# SCH_Yunis_PCB_2026-04-03.net
KiCad netlist of a schematic drawn in EasyEDA
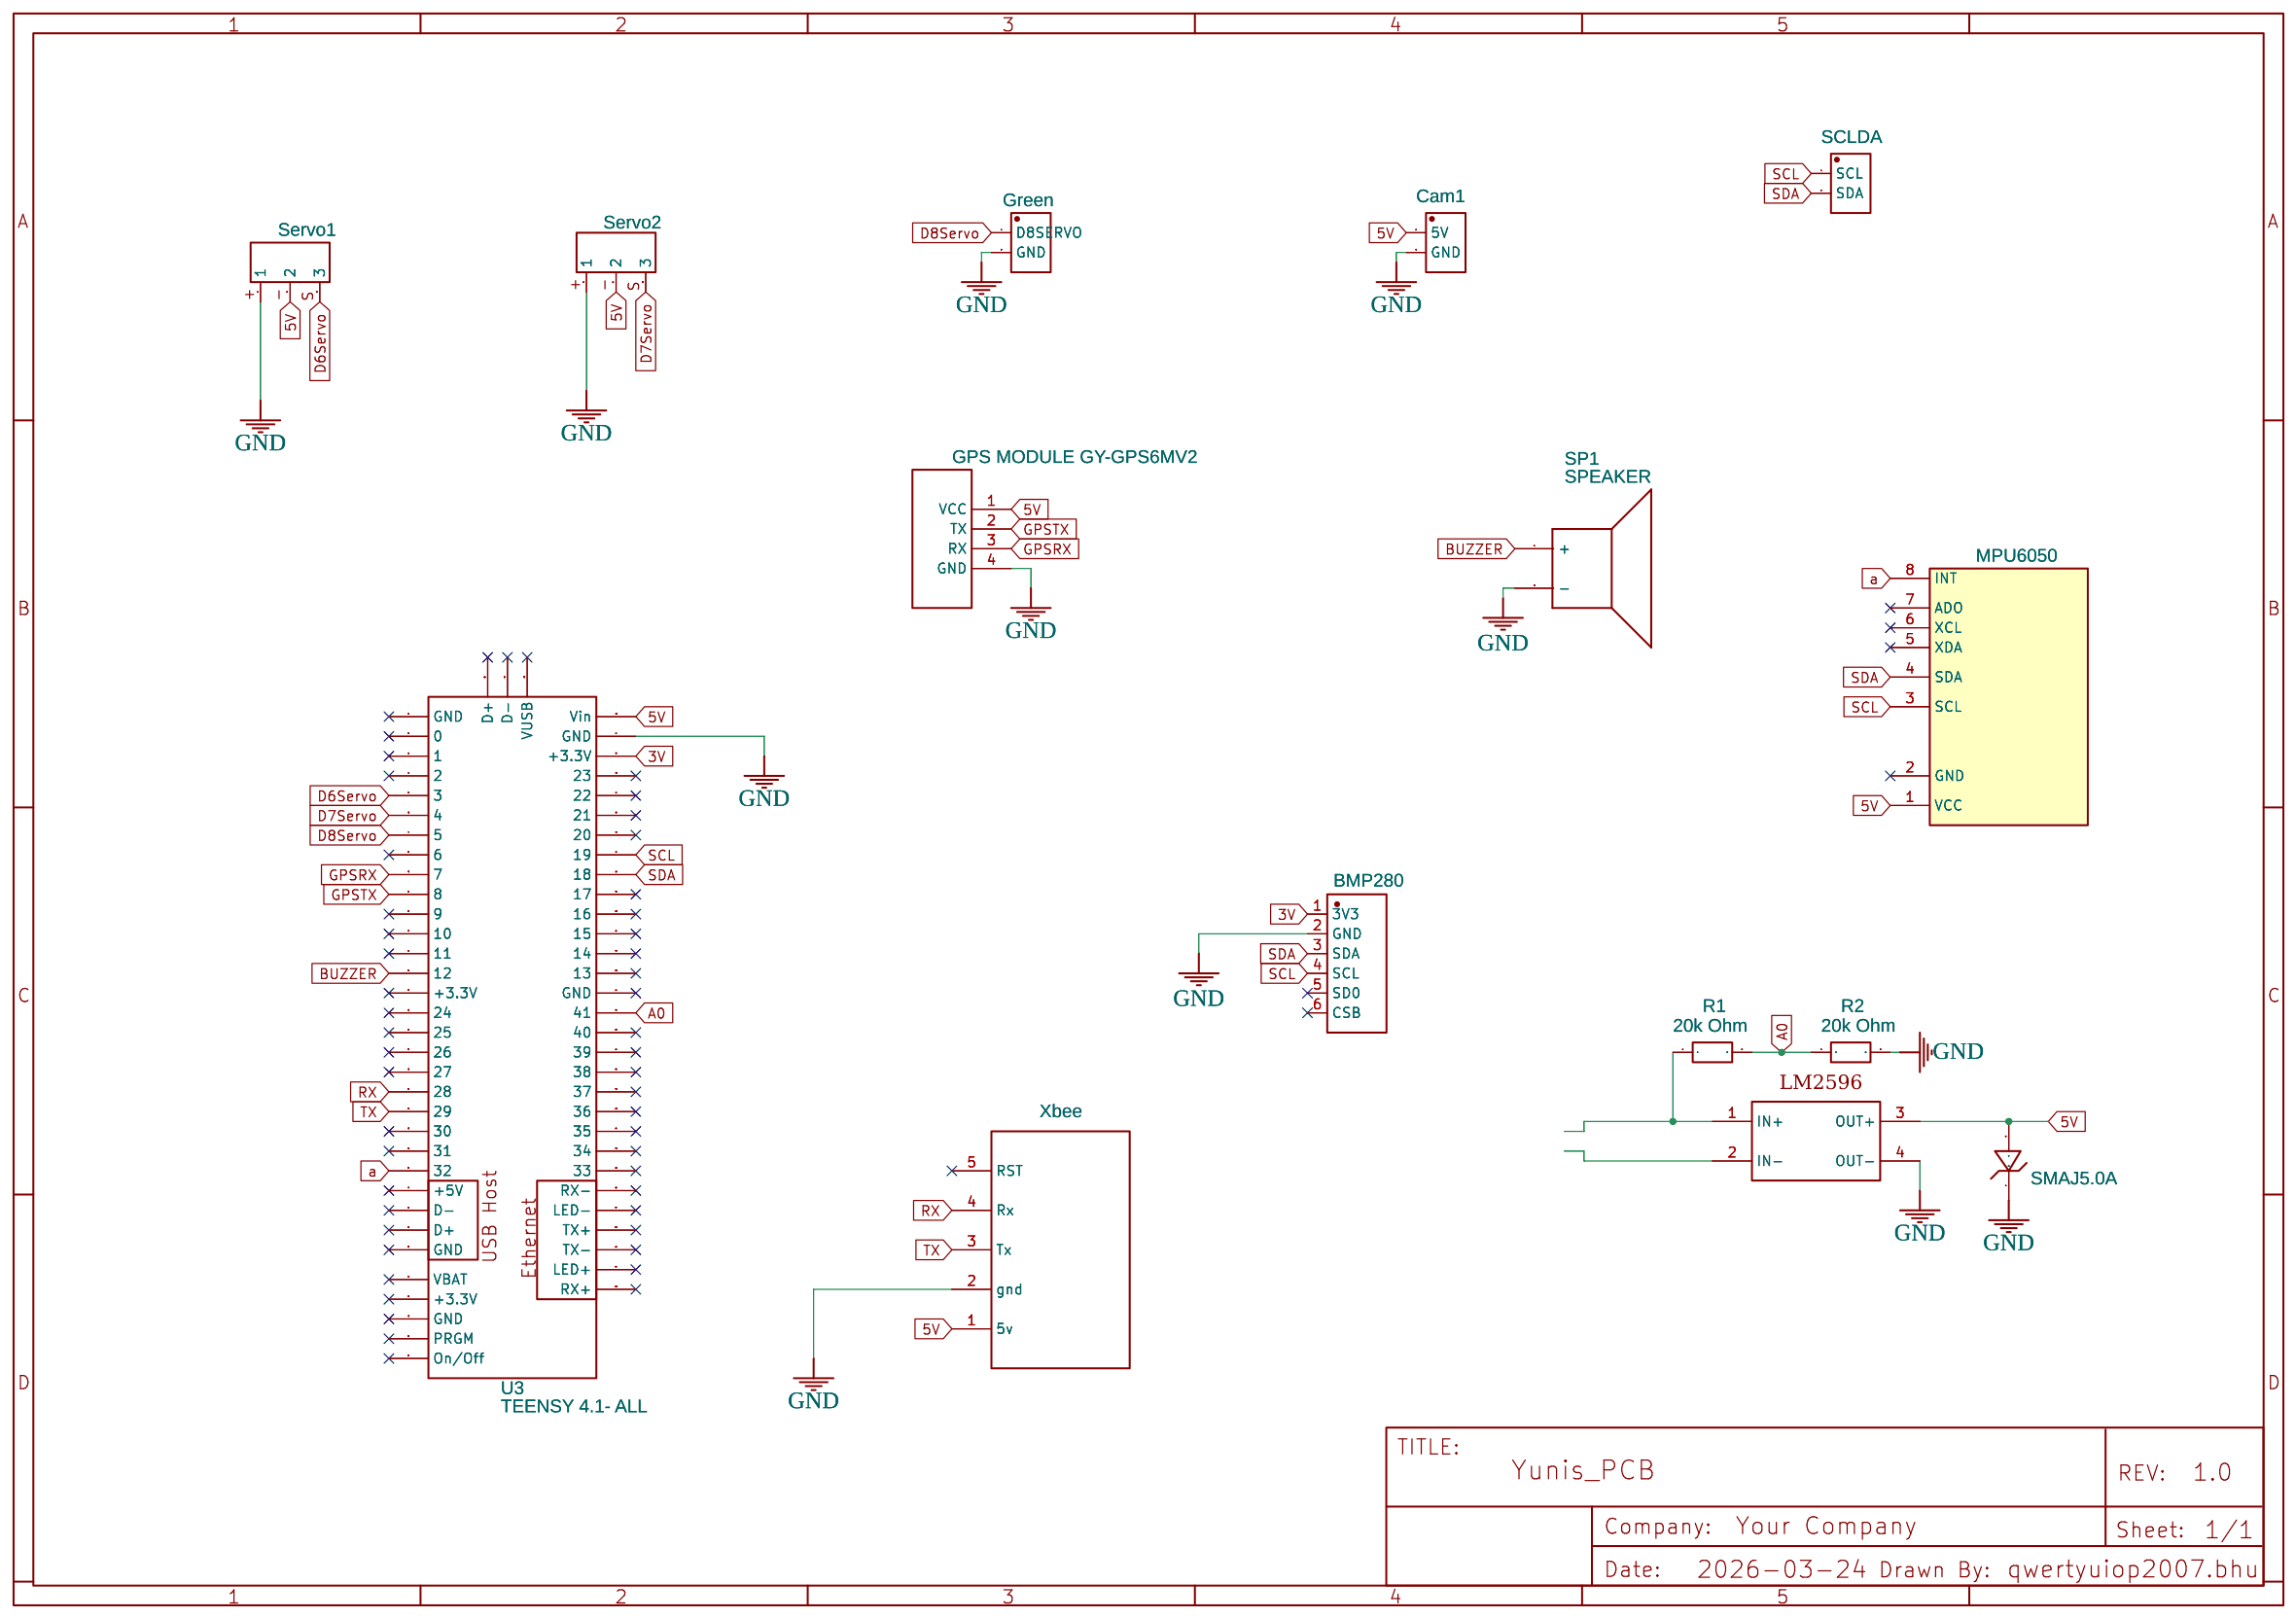
[diagram p0: schematic sheet]

(export (version "E")
  (design (tool "Eeschema 10.0.6"))
  (components
    (comp (ref "BUZZER1") (value "SCLDA") (libsource (lib "") (part "PINHEADER1x2_2")))
    (comp (ref "BUZZER2") (value "Cam1") (libsource (lib "") (part "PINHEADER1x2")))
    (comp (ref "BUZZER3") (value "Green") (libsource (lib "") (part "PINHEADER1x2_1")))
    (comp (ref "P1")
      (value "Servo2")
      (fields
        (field (name "Manufacturer Part") "Female headerHDR1X8-2.54")
        (field (name "Manufacturer") "BOOMELE")
      )
      (libsource (lib "") (part "HEADER PAD 3 PIN"))
    )
    (comp (ref "P2")
      (value "Servo1")
      (fields
        (field (name "Manufacturer Part") "Female headerHDR1X8-2.54")
        (field (name "Manufacturer") "BOOMELE")
      )
      (libsource (lib "") (part "HEADER PAD 3 PIN"))
    )
    (comp (ref "P3") (value "MPU6050") (libsource (lib "") (part "MPU6050")))
    (comp (ref "R1") (value "20k Ohm") (libsource (lib "") (part "R_0603_EU")))
    (comp (ref "R2") (value "20k Ohm") (libsource (lib "") (part "R_0603_EU")))
    (comp (ref "SP1") (value "SPEAKER") (libsource (lib "") (part "SPEAKER")))
    (comp (ref "U1") (value "GPS MODULE GY-GPS6MV2") (libsource (lib "") (part "GPS MODULE GY-GPS6MV2")))
    (comp (ref "U2") (value "BMP280") (libsource (lib "") (part "BMP280_C9900132626")))
    (comp (ref "U3") (value "TEENSY 4.1- ALL") (libsource (lib "") (part "TEENSY 4.1- ALL")))
    (comp (ref "U4")
      (value "BuckConverters_LM2596_Adj")
      (libsource (lib "") (part "BuckConverters_LM2596_Adj"))
    )
    (comp (ref "U5") (value "Xbee") (libsource (lib "") (part "Xbee Modulo")))
    (comp (ref "U6")
      (value "SMAJ5.0A")
      (fields (field (name "Manufacturer Part") "Littlefuse"))
      (libsource (lib "") (part "SMAJ5.0A"))
    )
  )
  (nets
    (net (code "1") (name "3V") (class "Default")
      (node (ref "U2") (pin "1") (pinfunction "3V3_1") (pintype "unspecified"))
      (node (ref "U3") (pin "46") (pinfunction "+3.3V_46") (pintype "unspecified"))
    )
    (net (code "2") (name "5V") (class "Default")
      (node (ref "BUZZER2") (pin "1") (pinfunction "5V_1") (pintype "unspecified"))
      (node (ref "P1") (pin "2") (pinfunction "2_2") (pintype "unspecified"))
      (node (ref "P2") (pin "2") (pinfunction "2_2") (pintype "unspecified"))
      (node (ref "P3") (pin "1") (pinfunction "VCC_1") (pintype "unspecified"))
      (node (ref "U1") (pin "1") (pinfunction "VCC_1") (pintype "unspecified"))
      (node (ref "U3") (pin "48") (pinfunction "Vin_48") (pintype "unspecified"))
      (node (ref "U4") (pin "3") (pinfunction "OUT+_3") (pintype "unspecified"))
      (node (ref "U5") (pin "1") (pinfunction "5v_1") (pintype "unspecified"))
      (node (ref "U6") (pin "2") (pinfunction "A_2") (pintype "unspecified"))
    )
    (net (code "3") (name "A0") (class "Default")
      (node (ref "R1") (pin "2") (pinfunction "2_2") (pintype "unspecified"))
      (node (ref "R2") (pin "1") (pinfunction "1_1") (pintype "unspecified"))
      (node (ref "U3") (pin "33") (pinfunction "41_33") (pintype "unspecified"))
    )
    (net (code "4") (name "BUZZER") (class "Default")
      (node (ref "SP1") (pin "1") (pinfunction "+_1") (pintype "bidirectional"))
      (node (ref "U3") (pin "14") (pinfunction "12_14") (pintype "unspecified"))
    )
    (net (code "5") (name "D6Servo") (class "Default")
      (node (ref "P2") (pin "3") (pinfunction "3_3") (pintype "unspecified"))
      (node (ref "U3") (pin "5") (pinfunction "3_5") (pintype "unspecified"))
    )
    (net (code "6") (name "D7Servo") (class "Default")
      (node (ref "P1") (pin "3") (pinfunction "3_3") (pintype "unspecified"))
      (node (ref "U3") (pin "6") (pinfunction "4_6") (pintype "unspecified"))
    )
    (net (code "7") (name "D8Servo") (class "Default")
      (node (ref "BUZZER3") (pin "1") (pinfunction "D8SERVO_1") (pintype "unspecified"))
      (node (ref "U3") (pin "7") (pinfunction "5_7") (pintype "unspecified"))
    )
    (net (code "8") (name "GND") (class "Default")
      (node (ref "BUZZER2") (pin "2") (pinfunction "GND_2") (pintype "unspecified"))
      (node (ref "BUZZER3") (pin "2") (pinfunction "GND_2") (pintype "unspecified"))
      (node (ref "P1") (pin "1") (pinfunction "1_1") (pintype "unspecified"))
      (node (ref "P2") (pin "1") (pinfunction "1_1") (pintype "unspecified"))
      (node (ref "R2") (pin "2") (pinfunction "2_2") (pintype "unspecified"))
      (node (ref "SP1") (pin "2") (pinfunction "-_2") (pintype "bidirectional"))
      (node (ref "U1") (pin "4") (pinfunction "GND_4") (pintype "unspecified"))
      (node (ref "U2") (pin "2") (pinfunction "GND_2") (pintype "unspecified"))
      (node (ref "U3") (pin "47") (pinfunction "GND_47") (pintype "unspecified"))
      (node (ref "U4") (pin "4") (pinfunction "OUT-_4") (pintype "unspecified"))
      (node (ref "U5") (pin "2") (pinfunction "gnd_2") (pintype "unspecified"))
      (node (ref "U6") (pin "1") (pinfunction "C_1") (pintype "unspecified"))
    )
    (net (code "9") (name "GPSRX") (class "Default")
      (node (ref "U1") (pin "3") (pinfunction "RX_3") (pintype "unspecified"))
      (node (ref "U3") (pin "9") (pinfunction "7_9") (pintype "unspecified"))
    )
    (net (code "10") (name "GPSTX") (class "Default")
      (node (ref "U1") (pin "2") (pinfunction "TX_2") (pintype "unspecified"))
      (node (ref "U3") (pin "10") (pinfunction "8_10") (pintype "unspecified"))
    )
    (net (code "11") (name "Net-(U4-IN+)") (class "Default")
      (node (ref "R1") (pin "1") (pinfunction "1_1") (pintype "unspecified"))
      (node (ref "U4") (pin "1") (pinfunction "IN+_1") (pintype "unspecified"))
    )
    (net (code "12") (name "RX") (class "Default")
      (node (ref "U3") (pin "20") (pinfunction "28_20") (pintype "unspecified"))
      (node (ref "U5") (pin "4") (pinfunction "Rx_4") (pintype "unspecified"))
    )
    (net (code "13") (name "SCL") (class "Default")
      (node (ref "BUZZER1") (pin "1") (pinfunction "SCL_1") (pintype "unspecified"))
      (node (ref "P3") (pin "3") (pinfunction "SCL_3") (pintype "unspecified"))
      (node (ref "U2") (pin "4") (pinfunction "SCL_4") (pintype "unspecified"))
      (node (ref "U3") (pin "41") (pinfunction "19_41") (pintype "unspecified"))
    )
    (net (code "14") (name "SDA") (class "Default")
      (node (ref "BUZZER1") (pin "2") (pinfunction "SDA_2") (pintype "unspecified"))
      (node (ref "P3") (pin "4") (pinfunction "SDA_4") (pintype "unspecified"))
      (node (ref "U2") (pin "3") (pinfunction "SDA_3") (pintype "unspecified"))
      (node (ref "U3") (pin "40") (pinfunction "18_40") (pintype "unspecified"))
    )
    (net (code "15") (name "TX") (class "Default")
      (node (ref "U3") (pin "21") (pinfunction "29_21") (pintype "unspecified"))
      (node (ref "U5") (pin "3") (pinfunction "Tx_3") (pintype "unspecified"))
    )
    (net (code "16") (name "a") (class "Default")
      (node (ref "P3") (pin "8") (pinfunction "INT_8") (pintype "unspecified"))
      (node (ref "U3") (pin "24") (pinfunction "32_24") (pintype "unspecified"))
    )
    (net (code "17") (name "unconnected-(P3-ADO-Pad7)") (class "Default")
      (node (ref "P3") (pin "7") (pinfunction "ADO_7") (pintype "unspecified+no_connect"))
    )
    (net (code "18") (name "unconnected-(P3-GND-Pad2)") (class "Default")
      (node (ref "P3") (pin "2") (pinfunction "GND_2") (pintype "unspecified+no_connect"))
    )
    (net (code "19") (name "unconnected-(P3-XCL-Pad6)") (class "Default")
      (node (ref "P3") (pin "6") (pinfunction "XCL_6") (pintype "unspecified+no_connect"))
    )
    (net (code "20") (name "unconnected-(P3-XDA-Pad5)") (class "Default")
      (node (ref "P3") (pin "5") (pinfunction "XDA_5") (pintype "unspecified+no_connect"))
    )
    (net (code "21") (name "unconnected-(U2-CSB-Pad6)") (class "Default")
      (node (ref "U2") (pin "6") (pinfunction "CSB_6") (pintype "unspecified+no_connect"))
    )
    (net (code "22") (name "unconnected-(U2-SD0-Pad5)") (class "Default")
      (node (ref "U2") (pin "5") (pinfunction "SD0_5") (pintype "unspecified+no_connect"))
    )
    (net (code "23") (name "unconnected-(U3-+3.3V-Pad15)") (class "Default")
      (node (ref "U3") (pin "15") (pinfunction "+3.3V_15") (pintype "unspecified+no_connect"))
    )
    (net (code "24") (name "unconnected-(U3-+3.3V-Pad73)") (class "Default")
      (node (ref "U3") (pin "73") (pinfunction "+3.3V_73") (pintype "unspecified+no_connect"))
    )
    (net (code "25") (name "unconnected-(U3-+5V-Pad71)") (class "Default")
      (node (ref "U3") (pin "71") (pinfunction "+5V_71") (pintype "unspecified+no_connect"))
    )
    (net (code "26") (name "unconnected-(U3-0-Pad2)") (class "Default")
      (node (ref "U3") (pin "2") (pinfunction "0_2") (pintype "unspecified+no_connect"))
    )
    (net (code "27") (name "unconnected-(U3-1-Pad3)") (class "Default")
      (node (ref "U3") (pin "3") (pinfunction "1_3") (pintype "unspecified+no_connect"))
    )
    (net (code "28") (name "unconnected-(U3-2-Pad4)") (class "Default")
      (node (ref "U3") (pin "4") (pinfunction "2_4") (pintype "unspecified+no_connect"))
    )
    (net (code "29") (name "unconnected-(U3-6-Pad8)") (class "Default")
      (node (ref "U3") (pin "8") (pinfunction "6_8") (pintype "unspecified+no_connect"))
    )
    (net (code "30") (name "unconnected-(U3-9-Pad11)") (class "Default")
      (node (ref "U3") (pin "11") (pinfunction "9_11") (pintype "unspecified+no_connect"))
    )
    (net (code "31") (name "unconnected-(U3-10-Pad12)") (class "Default")
      (node (ref "U3") (pin "12") (pinfunction "10_12") (pintype "unspecified+no_connect"))
    )
    (net (code "32") (name "unconnected-(U3-11-Pad13)") (class "Default")
      (node (ref "U3") (pin "13") (pinfunction "11_13") (pintype "unspecified+no_connect"))
    )
    (net (code "33") (name "unconnected-(U3-13-Pad35)") (class "Default")
      (node (ref "U3") (pin "35") (pinfunction "13_35") (pintype "unspecified+no_connect"))
    )
    (net (code "34") (name "unconnected-(U3-14-Pad36)") (class "Default")
      (node (ref "U3") (pin "36") (pinfunction "14_36") (pintype "unspecified+no_connect"))
    )
    (net (code "35") (name "unconnected-(U3-15-Pad37)") (class "Default")
      (node (ref "U3") (pin "37") (pinfunction "15_37") (pintype "unspecified+no_connect"))
    )
    (net (code "36") (name "unconnected-(U3-16-Pad38)") (class "Default")
      (node (ref "U3") (pin "38") (pinfunction "16_38") (pintype "unspecified+no_connect"))
    )
    (net (code "37") (name "unconnected-(U3-17-Pad39)") (class "Default")
      (node (ref "U3") (pin "39") (pinfunction "17_39") (pintype "unspecified+no_connect"))
    )
    (net (code "38") (name "unconnected-(U3-20-Pad42)") (class "Default")
      (node (ref "U3") (pin "42") (pinfunction "20_42") (pintype "unspecified+no_connect"))
    )
    (net (code "39") (name "unconnected-(U3-21-Pad43)") (class "Default")
      (node (ref "U3") (pin "43") (pinfunction "21_43") (pintype "unspecified+no_connect"))
    )
    (net (code "40") (name "unconnected-(U3-22-Pad44)") (class "Default")
      (node (ref "U3") (pin "44") (pinfunction "22_44") (pintype "unspecified+no_connect"))
    )
    (net (code "41") (name "unconnected-(U3-23-Pad45)") (class "Default")
      (node (ref "U3") (pin "45") (pinfunction "23_45") (pintype "unspecified+no_connect"))
    )
    (net (code "42") (name "unconnected-(U3-24-Pad16)") (class "Default")
      (node (ref "U3") (pin "16") (pinfunction "24_16") (pintype "unspecified+no_connect"))
    )
    (net (code "43") (name "unconnected-(U3-25-Pad17)") (class "Default")
      (node (ref "U3") (pin "17") (pinfunction "25_17") (pintype "unspecified+no_connect"))
    )
    (net (code "44") (name "unconnected-(U3-26-Pad18)") (class "Default")
      (node (ref "U3") (pin "18") (pinfunction "26_18") (pintype "unspecified+no_connect"))
    )
    (net (code "45") (name "unconnected-(U3-27-Pad19)") (class "Default")
      (node (ref "U3") (pin "19") (pinfunction "27_19") (pintype "unspecified+no_connect"))
    )
    (net (code "46") (name "unconnected-(U3-30-Pad22)") (class "Default")
      (node (ref "U3") (pin "22") (pinfunction "30_22") (pintype "unspecified+no_connect"))
    )
    (net (code "47") (name "unconnected-(U3-31-Pad23)") (class "Default")
      (node (ref "U3") (pin "23") (pinfunction "31_23") (pintype "unspecified+no_connect"))
    )
    (net (code "48") (name "unconnected-(U3-33-Pad25)") (class "Default")
      (node (ref "U3") (pin "25") (pinfunction "33_25") (pintype "unspecified+no_connect"))
    )
    (net (code "49") (name "unconnected-(U3-34-Pad26)") (class "Default")
      (node (ref "U3") (pin "26") (pinfunction "34_26") (pintype "unspecified+no_connect"))
    )
    (net (code "50") (name "unconnected-(U3-35-Pad27)") (class "Default")
      (node (ref "U3") (pin "27") (pinfunction "35_27") (pintype "unspecified+no_connect"))
    )
    (net (code "51") (name "unconnected-(U3-36-Pad28)") (class "Default")
      (node (ref "U3") (pin "28") (pinfunction "36_28") (pintype "unspecified+no_connect"))
    )
    (net (code "52") (name "unconnected-(U3-37-Pad29)") (class "Default")
      (node (ref "U3") (pin "29") (pinfunction "37_29") (pintype "unspecified+no_connect"))
    )
    (net (code "53") (name "unconnected-(U3-38-Pad30)") (class "Default")
      (node (ref "U3") (pin "30") (pinfunction "38_30") (pintype "unspecified+no_connect"))
    )
    (net (code "54") (name "unconnected-(U3-39-Pad31)") (class "Default")
      (node (ref "U3") (pin "31") (pinfunction "39_31") (pintype "unspecified+no_connect"))
    )
    (net (code "55") (name "unconnected-(U3-40-Pad32)") (class "Default")
      (node (ref "U3") (pin "32") (pinfunction "40_32") (pintype "unspecified+no_connect"))
    )
    (net (code "56") (name "unconnected-(U3-D+-Pad66)") (class "Default")
      (node (ref "U3") (pin "66") (pinfunction "D+_66") (pintype "unspecified+no_connect"))
    )
    (net (code "57") (name "unconnected-(U3-D+-Pad69)") (class "Default")
      (node (ref "U3") (pin "69") (pinfunction "D+_69") (pintype "unspecified+no_connect"))
    )
    (net (code "58") (name "unconnected-(U3-D--Pad67)") (class "Default")
      (node (ref "U3") (pin "67") (pinfunction "D-_67") (pintype "unspecified+no_connect"))
    )
    (net (code "59") (name "unconnected-(U3-D--Pad70)") (class "Default")
      (node (ref "U3") (pin "70") (pinfunction "D-_70") (pintype "unspecified+no_connect"))
    )
    (net (code "60") (name "unconnected-(U3-GND-Pad1)") (class "Default")
      (node (ref "U3") (pin "1") (pinfunction "GND_1") (pintype "unspecified+no_connect"))
    )
    (net (code "61") (name "unconnected-(U3-GND-Pad34)") (class "Default")
      (node (ref "U3") (pin "34") (pinfunction "GND_34") (pintype "unspecified+no_connect"))
    )
    (net (code "62") (name "unconnected-(U3-GND-Pad49)") (class "Default")
      (node (ref "U3") (pin "49") (pinfunction "GND_49") (pintype "unspecified+no_connect"))
    )
    (net (code "63") (name "unconnected-(U3-GND-Pad68)") (class "Default")
      (node (ref "U3") (pin "68") (pinfunction "GND_68") (pintype "unspecified+no_connect"))
    )
    (net (code "64") (name "unconnected-(U3-LED+-Pad61)") (class "Default")
      (node (ref "U3") (pin "61") (pinfunction "LED+_61") (pintype "unspecified+no_connect"))
    )
    (net (code "65") (name "unconnected-(U3-LED--Pad64)") (class "Default")
      (node (ref "U3") (pin "64") (pinfunction "LED-_64") (pintype "unspecified+no_connect"))
    )
    (net (code "66") (name "unconnected-(U3-On{slash}Off-Pad51)") (class "Default")
      (node (ref "U3") (pin "51") (pinfunction "On/Off_51") (pintype "unspecified+no_connect"))
    )
    (net (code "67") (name "unconnected-(U3-PRGM-Pad50)") (class "Default")
      (node (ref "U3") (pin "50") (pinfunction "PRGM_50") (pintype "unspecified+no_connect"))
    )
    (net (code "68") (name "unconnected-(U3-RX+-Pad60)") (class "Default")
      (node (ref "U3") (pin "60") (pinfunction "RX+_60") (pintype "unspecified+no_connect"))
    )
    (net (code "69") (name "unconnected-(U3-RX--Pad65)") (class "Default")
      (node (ref "U3") (pin "65") (pinfunction "RX-_65") (pintype "unspecified+no_connect"))
    )
    (net (code "70") (name "unconnected-(U3-TX+-Pad63)") (class "Default")
      (node (ref "U3") (pin "63") (pinfunction "TX+_63") (pintype "unspecified+no_connect"))
    )
    (net (code "71") (name "unconnected-(U3-TX--Pad62)") (class "Default")
      (node (ref "U3") (pin "62") (pinfunction "TX-_62") (pintype "unspecified+no_connect"))
    )
    (net (code "72") (name "unconnected-(U3-VBAT-Pad72)") (class "Default")
      (node (ref "U3") (pin "72") (pinfunction "VBAT_72") (pintype "unspecified+no_connect"))
    )
    (net (code "73") (name "unconnected-(U3-VUSB-Pad52)") (class "Default")
      (node (ref "U3") (pin "52") (pinfunction "VUSB_52") (pintype "unspecified+no_connect"))
    )
    (net (code "74") (name "unconnected-(U4-IN--Pad2)") (class "Default")
      (node (ref "U4") (pin "2") (pinfunction "IN-_2") (pintype "unspecified"))
    )
    (net (code "75") (name "unconnected-(U5-RST-Pad5)") (class "Default")
      (node (ref "U5") (pin "5") (pinfunction "RST_5") (pintype "unspecified+no_connect"))
    )
  )
)
